# main.net
KiCad netlist of a schematic drawn in EasyEDA Pro
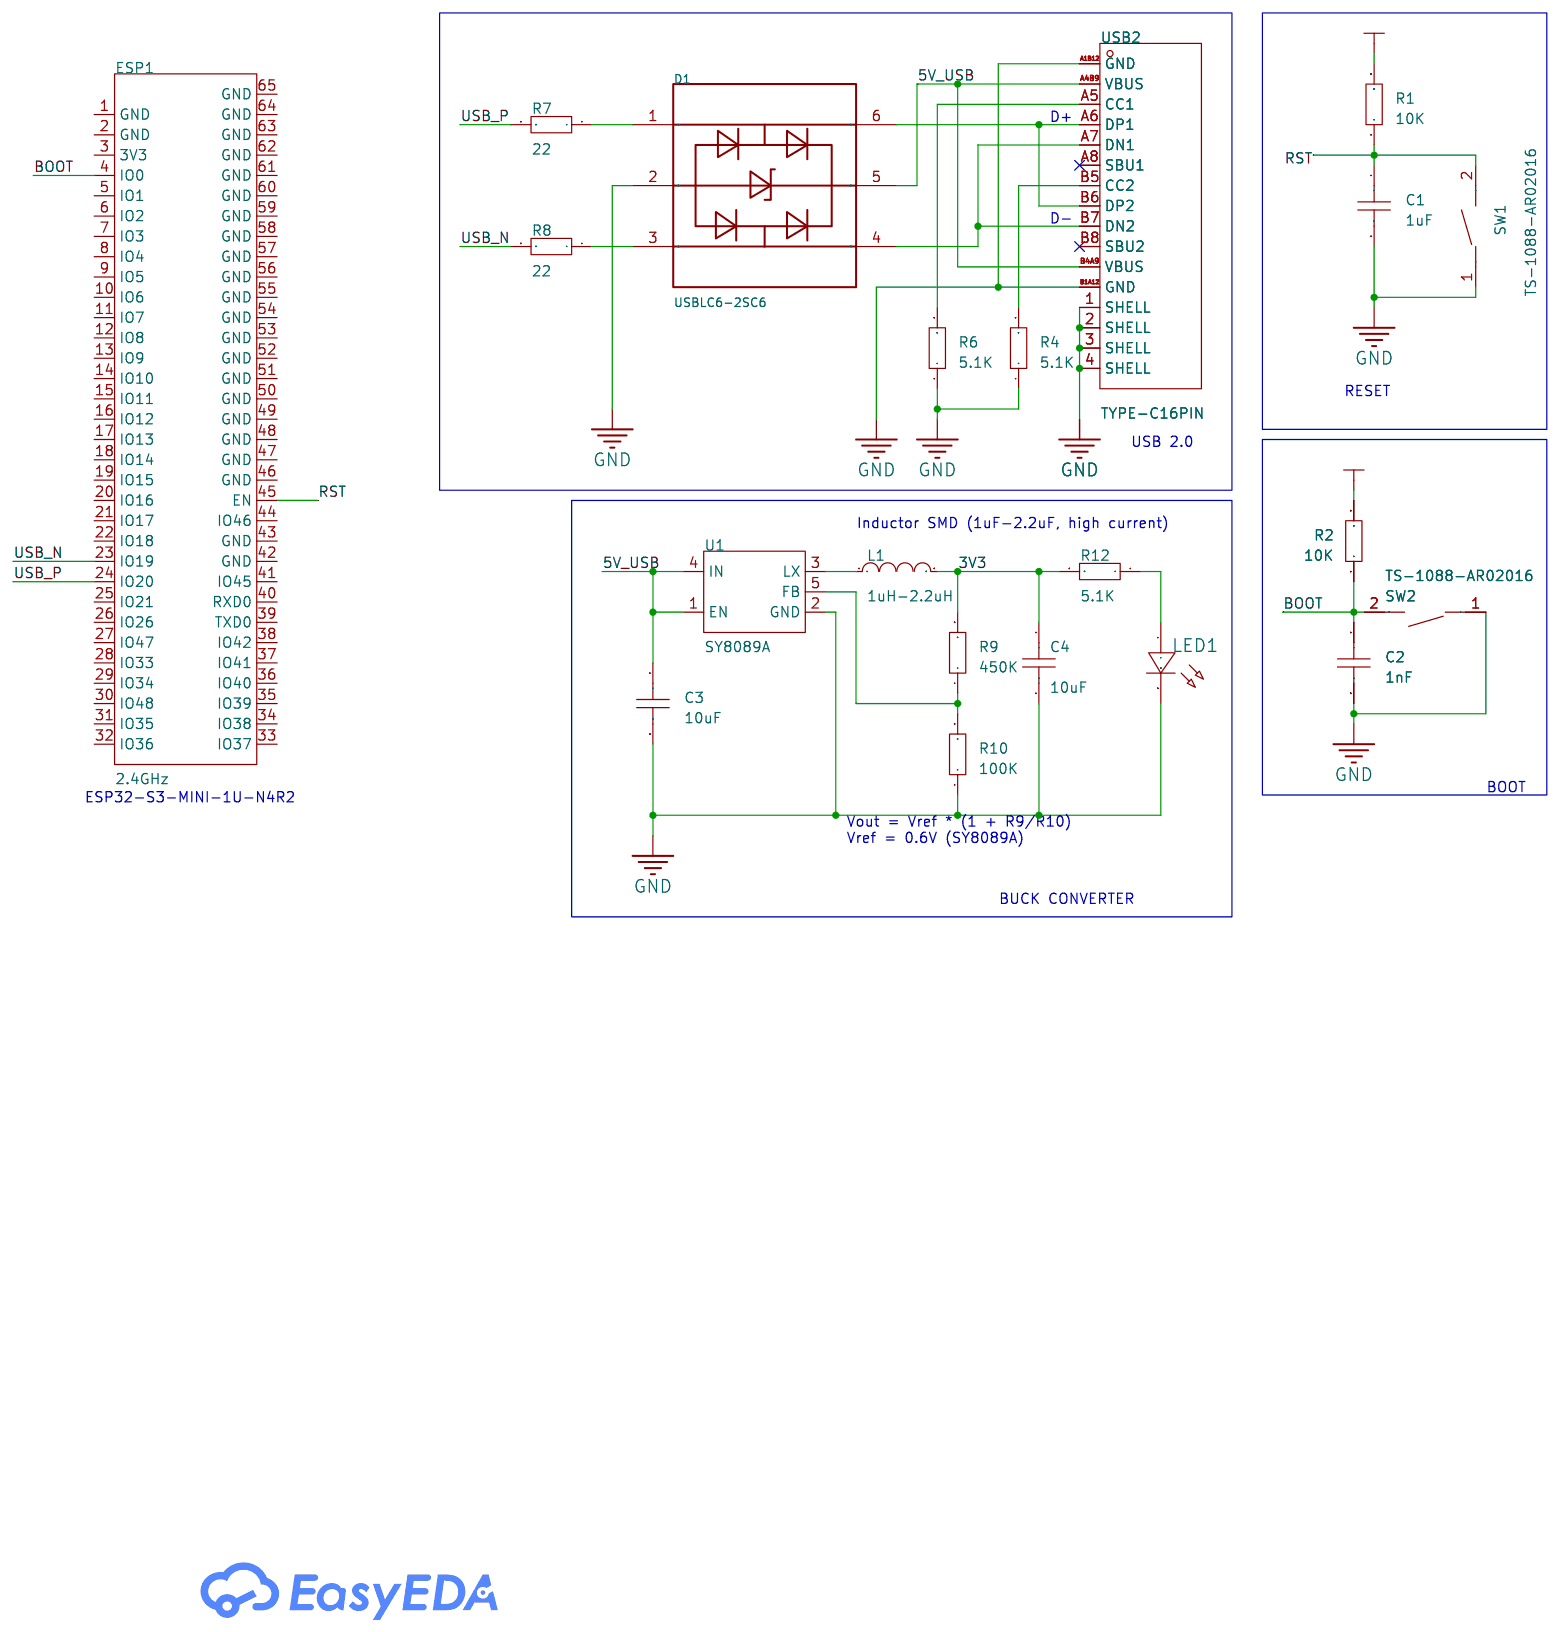
[diagram p0: ESP32-S3-Mini-1U-N4R2]
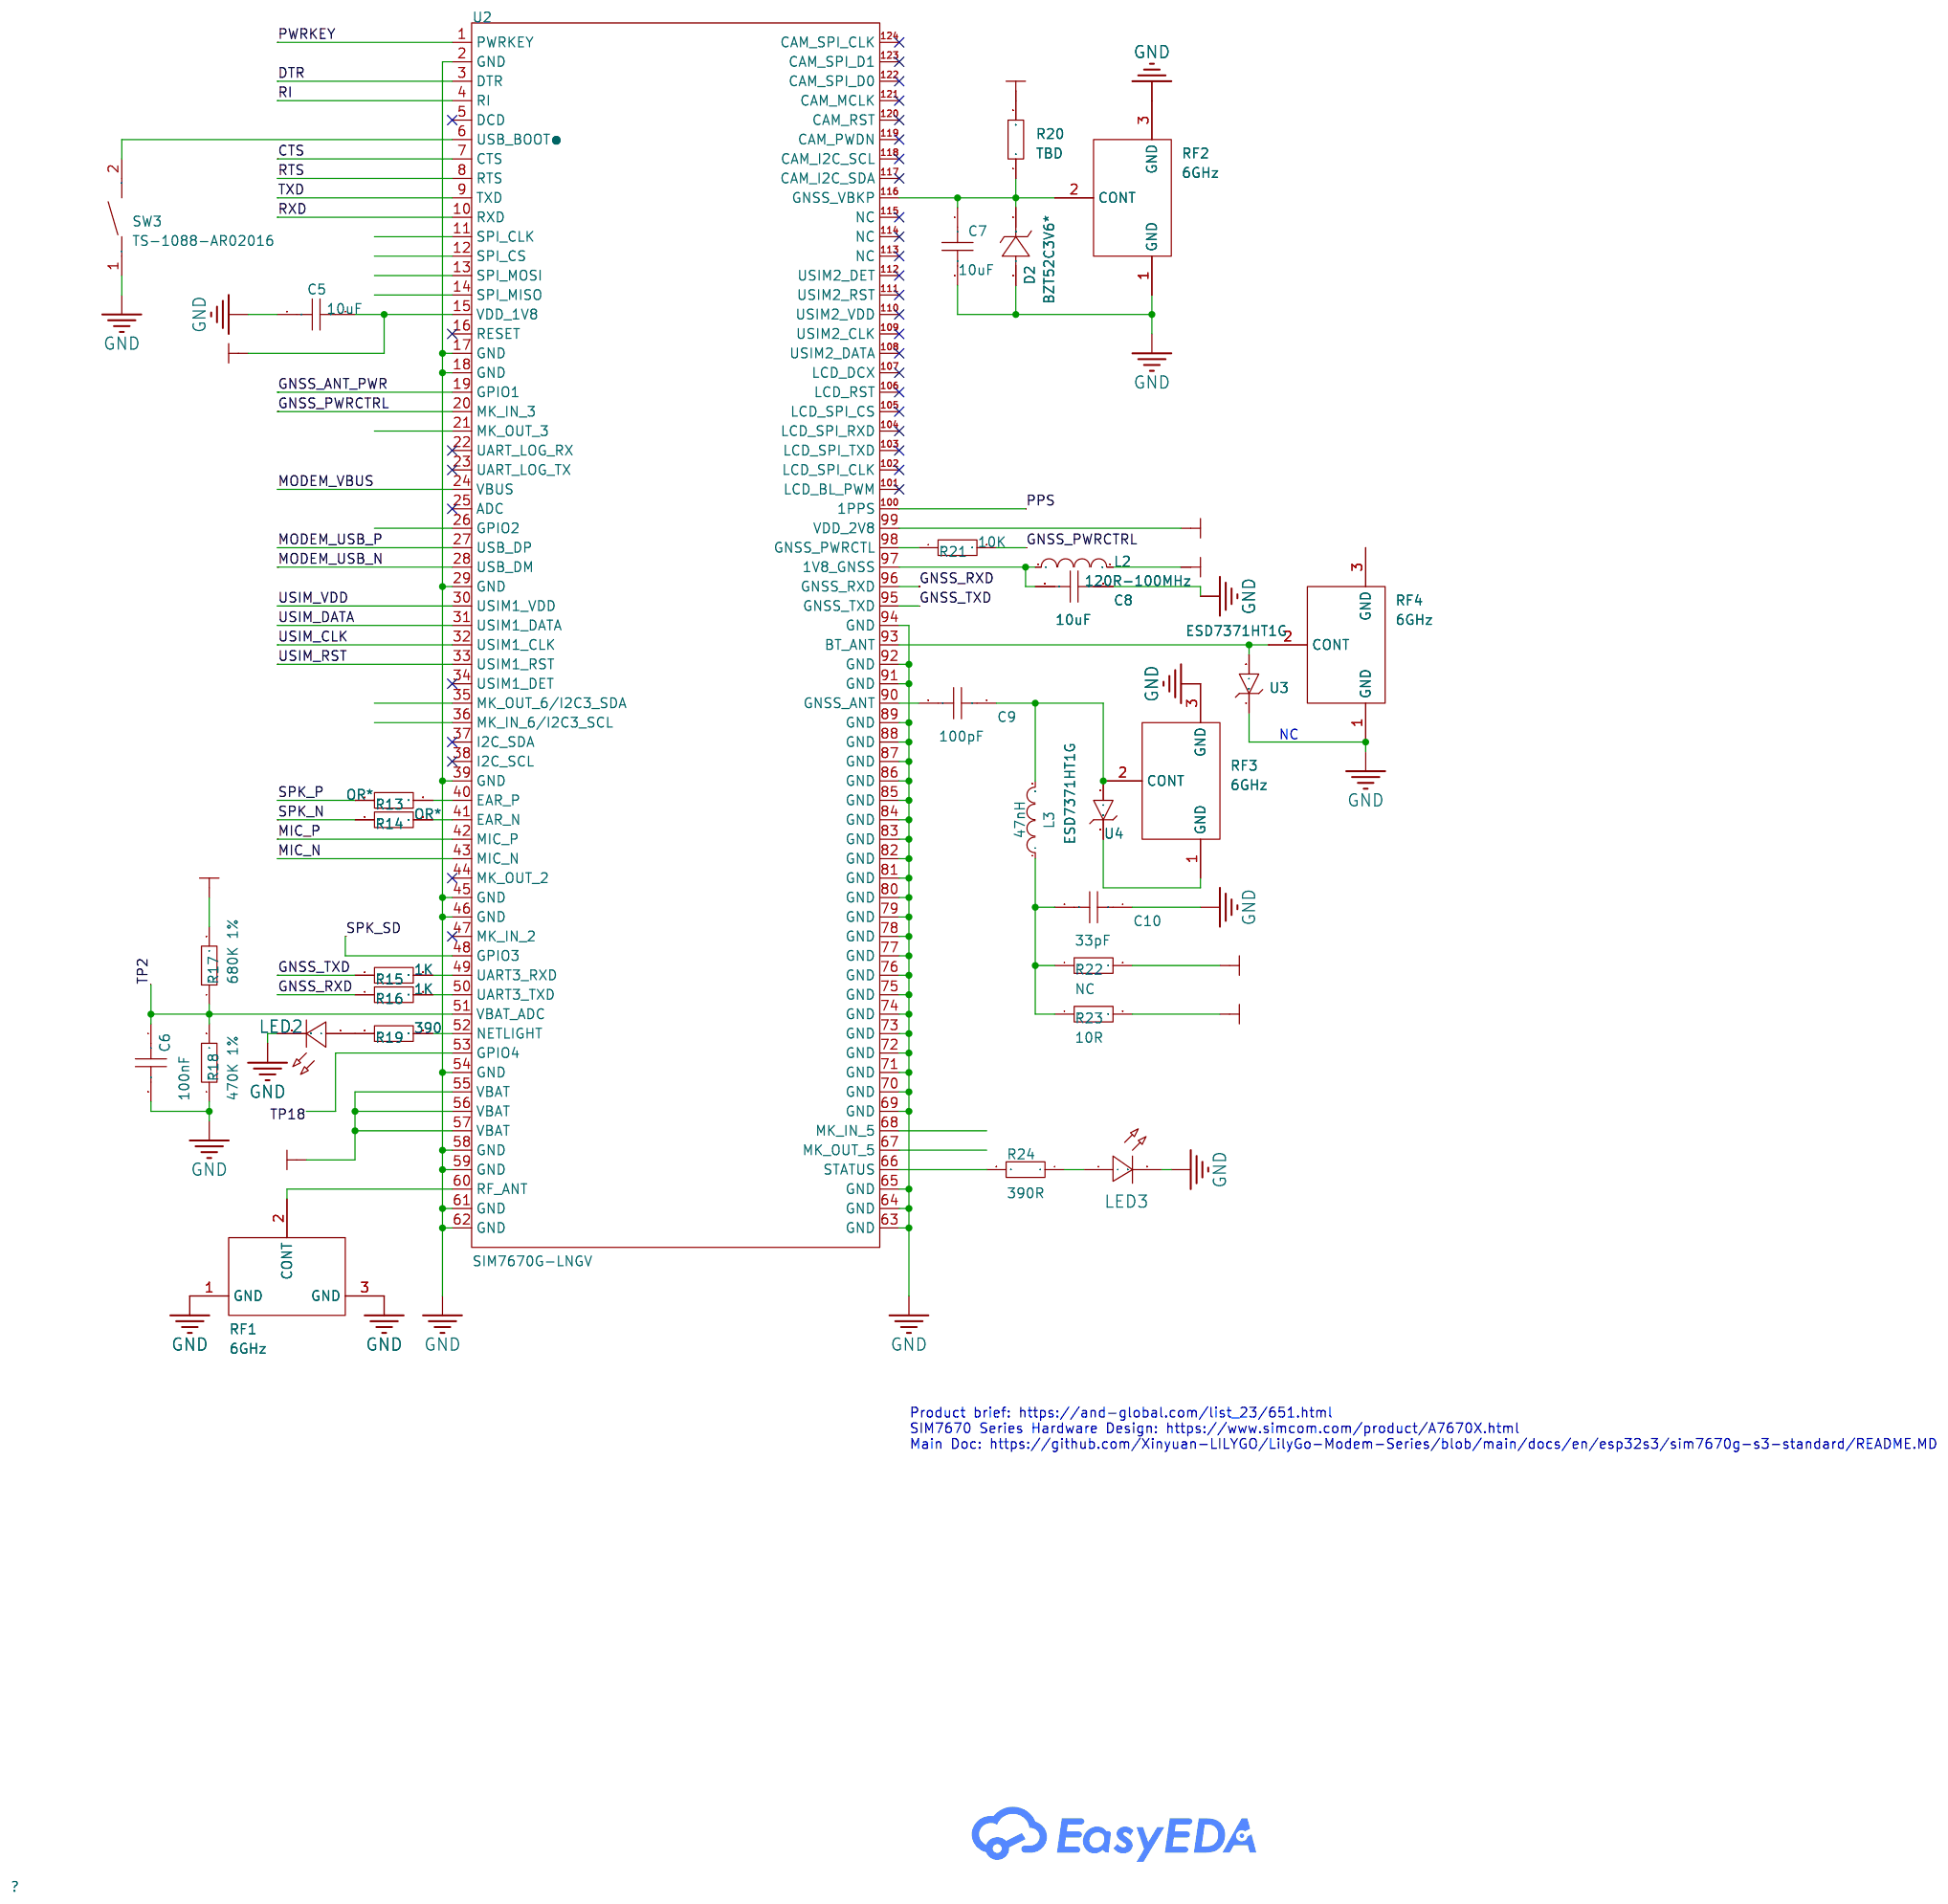
[diagram p1: SIM7670G]
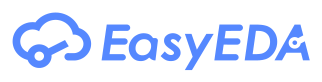
[diagram p2: SIM7670C]

(export (version "E")
  (design (tool "Eeschema 10.0.6"))
  (components
    (comp (ref "C1")
      (value "1uF")
      (footprint "easyedapro:C0603")
      (libsource (lib "easyedapro") (part "CAP_OLD"))
    )
    (comp (ref "C2")
      (value "1nF")
      (footprint "easyedapro:C0603")
      (libsource (lib "easyedapro") (part "CAP_OLD"))
    )
    (comp (ref "C3")
      (value "10uF")
      (footprint "easyedapro:C0603")
      (libsource (lib "easyedapro") (part "CAP_OLD"))
    )
    (comp (ref "C4")
      (value "10uF")
      (footprint "easyedapro:C0603")
      (libsource (lib "easyedapro") (part "CAP_OLD"))
    )
    (comp (ref "D1")
      (value "USBLC6-2SC6")
      (footprint "easyedapro:TSOT-23-6_L2.9-W1.6-P0.95-LS2.8-BR")
      (fields (field (name "Manufacturer") "Slkor(萨科微)"))
      (libsource (lib "easyedapro") (part "USBLC6-2SC6_C48971164"))
    )
    (comp (ref "ESP1")
      (value "2.4GHz")
      (footprint "easyedapro:BULETM-SMD_ESPRESSIF_ESP32-S3-MINI-1U-N8")
      (fields
        (field (name "Manufacturer Part") "ESP32-S3-MINI-1U-N4R2")
        (field (name "Manufacturer") "ESPRESSIF(乐鑫)")
      )
      (libsource (lib "easyedapro") (part "ESP32-S3-MINI-1U-N4R2"))
    )
    (comp (ref "L1")
      (value "1uH-2.2uH")
      (footprint "easyedapro:L0603")
      (libsource (lib "easyedapro") (part "电感"))
    )
    (comp (ref "LED1")
      (value "~")
      (footprint "easyedapro:LED0402-RD_YELLOW")
      (libsource (lib "easyedapro") (part "LED_R"))
    )
    (comp (ref "R1") (value "10K") (footprint "easyedapro:R0603") (libsource (lib "easyedapro") (part "Res")))
    (comp (ref "R2") (value "10K") (footprint "easyedapro:R0603") (libsource (lib "easyedapro") (part "Res")))
    (comp (ref "R4")
      (value "5.1K")
      (footprint "easyedapro:R0603")
      (libsource (lib "easyedapro") (part "Res"))
    )
    (comp (ref "R6")
      (value "5.1K")
      (footprint "easyedapro:R0603")
      (libsource (lib "easyedapro") (part "Res"))
    )
    (comp (ref "R7") (value "22") (footprint "easyedapro:R0603") (libsource (lib "easyedapro") (part "Res")))
    (comp (ref "R8") (value "22") (footprint "easyedapro:R0603") (libsource (lib "easyedapro") (part "Res")))
    (comp (ref "R9")
      (value "450K")
      (footprint "easyedapro:R0603")
      (libsource (lib "easyedapro") (part "Res"))
    )
    (comp (ref "R10")
      (value "100K")
      (footprint "easyedapro:R0603")
      (libsource (lib "easyedapro") (part "Res"))
    )
    (comp (ref "R12")
      (value "5.1K")
      (footprint "easyedapro:R0603")
      (libsource (lib "easyedapro") (part "Res"))
    )
    (comp (ref "SW1")
      (value "TS-1088-AR02016")
      (footprint "easyedapro:SW-SMD_L3.9-W3.0-P4.45")
      (fields (field (name "Manufacturer") "XUNPU(讯普)"))
      (libsource (lib "easyedapro") (part "TS-1088-AR02016"))
    )
    (comp (ref "SW2")
      (value "TS-1088-AR02016")
      (footprint "easyedapro:SW-SMD_L3.9-W3.0-P4.45")
      (fields (field (name "Manufacturer") "XUNPU(讯普)"))
      (libsource (lib "easyedapro") (part "TS-1088-AR02016"))
    )
    (comp (ref "U1")
      (value "SY8089A")
      (footprint "easyedapro:SOT-23-5_L3.0-W1.7-P0.95-LS2.8-BL")
      (fields (field (name "Manufacturer") "TECH PUBLIC(台舟)"))
      (libsource (lib "easyedapro") (part "SY8089A"))
    )
    (comp (ref "USB2")
      (value "TYPE-C16PIN")
      (footprint "easyedapro:USB-C-SMD_TYPE-C16PIN")
      (fields (field (name "Manufacturer") "SHOU HAN(首韩)"))
      (libsource (lib "easyedapro") (part "TYPE-C16PIN"))
    )
    (comp (ref "C5")
      (value "10uF")
      (footprint "easyedapro:C0603")
      (libsource (lib "easyedapro") (part "CAP_OLD"))
    )
    (comp (ref "C6")
      (value "100nF")
      (footprint "easyedapro:C0603")
      (libsource (lib "easyedapro") (part "CAP_OLD"))
    )
    (comp (ref "C7")
      (value "10uF")
      (footprint "easyedapro:C0603")
      (libsource (lib "easyedapro") (part "CAP_OLD"))
    )
    (comp (ref "C8")
      (value "10uF")
      (footprint "easyedapro:C0603")
      (libsource (lib "easyedapro") (part "CAP_OLD"))
    )
    (comp (ref "C9")
      (value "100pF")
      (footprint "easyedapro:C0603")
      (libsource (lib "easyedapro") (part "CAP_OLD"))
    )
    (comp (ref "C10")
      (value "33pF")
      (footprint "easyedapro:C0603")
      (libsource (lib "easyedapro") (part "CAP_OLD"))
    )
    (comp (ref "D2")
      (value "BZT52C3V6*")
      (footprint "easyedapro:SOD-123_L2.8-W1.8-LS3.7-RD")
      (fields (field (name "Manufacturer") "PAKER(派克微)"))
      (libsource (lib "easyedapro") (part "BZT52C3V6_C49652771"))
    )
    (comp (ref "L2")
      (value "120R-100MHz")
      (footprint "easyedapro:L0603")
      (libsource (lib "easyedapro") (part "电感"))
    )
    (comp (ref "L3") (value "47nH") (footprint "easyedapro:L0603") (libsource (lib "easyedapro") (part "电感")))
    (comp (ref "LED2")
      (value "~")
      (footprint "easyedapro:LED0402-RD_YELLOW")
      (libsource (lib "easyedapro") (part "LED_R"))
    )
    (comp (ref "LED3")
      (value "~")
      (footprint "easyedapro:LED0402-RD_YELLOW")
      (libsource (lib "easyedapro") (part "LED_R"))
    )
    (comp (ref "R13")
      (value "OR*")
      (footprint "easyedapro:R0603")
      (libsource (lib "easyedapro") (part "Res"))
    )
    (comp (ref "R14")
      (value "OR*")
      (footprint "easyedapro:R0603")
      (libsource (lib "easyedapro") (part "Res"))
    )
    (comp (ref "R15") (value "1K") (footprint "easyedapro:R0603") (libsource (lib "easyedapro") (part "Res")))
    (comp (ref "R16") (value "1K") (footprint "easyedapro:R0603") (libsource (lib "easyedapro") (part "Res")))
    (comp (ref "R17")
      (value "680K 1%")
      (footprint "easyedapro:R0603")
      (libsource (lib "easyedapro") (part "Res"))
    )
    (comp (ref "R18")
      (value "470K 1%")
      (footprint "easyedapro:R0603")
      (libsource (lib "easyedapro") (part "Res"))
    )
    (comp (ref "R19")
      (value "390")
      (footprint "easyedapro:R0603")
      (libsource (lib "easyedapro") (part "Res"))
    )
    (comp (ref "R20")
      (value "TBD")
      (footprint "easyedapro:R0603")
      (libsource (lib "easyedapro") (part "Res"))
    )
    (comp (ref "R21")
      (value "10K")
      (footprint "easyedapro:R0603")
      (libsource (lib "easyedapro") (part "Res"))
    )
    (comp (ref "R22") (value "NC") (footprint "easyedapro:R0603") (libsource (lib "easyedapro") (part "Res")))
    (comp (ref "R23")
      (value "10R")
      (footprint "easyedapro:R0603")
      (libsource (lib "easyedapro") (part "Res"))
    )
    (comp (ref "R24")
      (value "390R")
      (footprint "easyedapro:R0603")
      (libsource (lib "easyedapro") (part "Res"))
    )
    (comp (ref "RF1")
      (value "6GHz")
      (footprint "easyedapro:ANT-SMD_UFL-R-SMT01")
      (fields (field (name "Manufacturer Part") "U.FL-R-SMT(01)") (field (name "Manufacturer") "HRS(广濑)"))
      (libsource (lib "easyedapro") (part "U.FL-R-SMT(01)"))
    )
    (comp (ref "RF2")
      (value "6GHz")
      (footprint "easyedapro:ANT-SMD_UFL-R-SMT01")
      (fields (field (name "Manufacturer Part") "U.FL-R-SMT(01)") (field (name "Manufacturer") "HRS(广濑)"))
      (libsource (lib "easyedapro") (part "U.FL-R-SMT(01)"))
    )
    (comp (ref "RF3")
      (value "6GHz")
      (footprint "easyedapro:ANT-SMD_UFL-R-SMT01")
      (fields (field (name "Manufacturer Part") "U.FL-R-SMT(01)") (field (name "Manufacturer") "HRS(广濑)"))
      (libsource (lib "easyedapro") (part "U.FL-R-SMT(01)"))
    )
    (comp (ref "RF4")
      (value "6GHz")
      (footprint "easyedapro:ANT-SMD_UFL-R-SMT01")
      (fields (field (name "Manufacturer Part") "U.FL-R-SMT(01)") (field (name "Manufacturer") "HRS(广濑)"))
      (libsource (lib "easyedapro") (part "U.FL-R-SMT(01)"))
    )
    (comp (ref "SW3")
      (value "TS-1088-AR02016")
      (footprint "easyedapro:SW-SMD_L3.9-W3.0-P4.45")
      (fields (field (name "Manufacturer") "XUNPU(讯普)"))
      (libsource (lib "easyedapro") (part "TS-1088-AR02016"))
    )
    (comp (ref "U2")
      (value "SIM7670G-LNGV")
      (footprint "easyedapro:LCC-124_L24.0-W24.0-P1.0-TL")
      (fields (field (name "Manufacturer") "SIMCOM(芯讯通无线科技)"))
      (libsource (lib "easyedapro") (part "SIM7670G-LNGV"))
    )
    (comp (ref "U3")
      (value "ESD7371HT1G")
      (footprint "easyedapro:SOD-323_L1.7-W1.3-LS2.5-RD")
      (fields (field (name "Manufacturer") "onsemi(安森美)"))
      (libsource (lib "easyedapro") (part "ESD7371HT1G"))
    )
    (comp (ref "U4")
      (value "ESD7371HT1G")
      (footprint "easyedapro:SOD-323_L1.7-W1.3-LS2.5-RD")
      (fields (field (name "Manufacturer") "onsemi(安森美)"))
      (libsource (lib "easyedapro") (part "ESD7371HT1G"))
    )
  )
  (nets
    (net (code "1") (name "+1.8V") (class "Default")
      (node (ref "C5") (pin "1") (pinfunction "1_1") (pintype "input"))
      (node (ref "U2") (pin "15") (pinfunction "VDD_1V8_15") (pintype "unspecified"))
    )
    (net (code "2") (name "+1V8") (class "Default")
      (node (ref "L2") (pin "2") (pinfunction "2_2") (pintype "input"))
    )
    (net (code "3") (name "+3V6") (class "Default")
      (node (ref "U2") (pin "55") (pinfunction "VBAT_55") (pintype "unspecified"))
      (node (ref "U2") (pin "56") (pinfunction "VBAT_56") (pintype "unspecified"))
      (node (ref "U2") (pin "57") (pinfunction "VBAT_57") (pintype "unspecified"))
    )
    (net (code "4") (name "3.3V") (class "Default")
      (node (ref "R1") (pin "2") (pinfunction "2_2") (pintype "input"))
      (node (ref "R2") (pin "2") (pinfunction "2_2") (pintype "input"))
    )
    (net (code "5") (name "3V3") (class "Default")
      (node (ref "C4") (pin "1") (pinfunction "1_1") (pintype "input"))
      (node (ref "L1") (pin "2") (pinfunction "2_2") (pintype "input"))
      (node (ref "R12") (pin "2") (pinfunction "2_2") (pintype "input"))
      (node (ref "R9") (pin "2") (pinfunction "2_2") (pintype "input"))
    )
    (net (code "6") (name "5V_USB") (class "Default")
      (node (ref "C3") (pin "1") (pinfunction "1_1") (pintype "input"))
      (node (ref "D1") (pin "5") (pinfunction "VBUS_5") (pintype "input"))
      (node (ref "U1") (pin "1") (pinfunction "EN_1") (pintype "unspecified"))
      (node (ref "U1") (pin "4") (pinfunction "IN_4") (pintype "unspecified"))
      (node (ref "USB2") (pin "A4B9") (pinfunction "VBUS_A4B9") (pintype "unspecified"))
      (node (ref "USB2") (pin "B4A9") (pinfunction "VBUS_B4A9") (pintype "unspecified"))
    )
    (net (code "7") (name "BOOT") (class "Default")
      (node (ref "C2") (pin "1") (pinfunction "1_1") (pintype "input"))
      (node (ref "ESP1") (pin "4") (pinfunction "IO0_4") (pintype "unspecified"))
      (node (ref "R2") (pin "1") (pinfunction "1_1") (pintype "input"))
      (node (ref "SW2") (pin "2") (pinfunction "2_2") (pintype "unspecified"))
    )
    (net (code "8") (name "CTS") (class "Default")
      (node (ref "U2") (pin "7") (pinfunction "CTS_7") (pintype "unspecified"))
    )
    (net (code "9") (name "DTR") (class "Default")
      (node (ref "U2") (pin "3") (pinfunction "DTR_3") (pintype "unspecified"))
    )
    (net (code "10") (name "GND") (class "Default")
      (node (ref "C1") (pin "2") (pinfunction "2_2") (pintype "input"))
      (node (ref "C10") (pin "1") (pinfunction "1_1") (pintype "input"))
      (node (ref "C2") (pin "2") (pinfunction "2_2") (pintype "input"))
      (node (ref "C3") (pin "2") (pinfunction "2_2") (pintype "input"))
      (node (ref "C4") (pin "2") (pinfunction "2_2") (pintype "input"))
      (node (ref "C5") (pin "2") (pinfunction "2_2") (pintype "input"))
      (node (ref "C6") (pin "2") (pinfunction "2_2") (pintype "input"))
      (node (ref "C7") (pin "2") (pinfunction "2_2") (pintype "input"))
      (node (ref "C8") (pin "1") (pinfunction "1_1") (pintype "input"))
      (node (ref "D1") (pin "2") (pinfunction "GND_2") (pintype "input"))
      (node (ref "D2") (pin "2") (pinfunction "A_2") (pintype "unspecified"))
      (node (ref "LED1") (pin "2") (pinfunction "C_2") (pintype "input"))
      (node (ref "LED2") (pin "2") (pinfunction "C_2") (pintype "input"))
      (node (ref "LED3") (pin "2") (pinfunction "C_2") (pintype "input"))
      (node (ref "R10") (pin "1") (pinfunction "1_1") (pintype "input"))
      (node (ref "R18") (pin "1") (pinfunction "1_1") (pintype "input"))
      (node (ref "R4") (pin "1") (pinfunction "1_1") (pintype "input"))
      (node (ref "R6") (pin "1") (pinfunction "1_1") (pintype "input"))
      (node (ref "RF1") (pin "1") (pinfunction "GND_1") (pintype "unspecified"))
      (node (ref "RF1") (pin "3") (pinfunction "GND_3") (pintype "unspecified"))
      (node (ref "RF2") (pin "1") (pinfunction "GND_1") (pintype "unspecified"))
      (node (ref "RF2") (pin "3") (pinfunction "GND_3") (pintype "unspecified"))
      (node (ref "RF3") (pin "3") (pinfunction "GND_3") (pintype "unspecified"))
      (node (ref "RF4") (pin "1") (pinfunction "GND_1") (pintype "unspecified"))
      (node (ref "SW1") (pin "1") (pinfunction "1_1") (pintype "unspecified"))
      (node (ref "SW2") (pin "1") (pinfunction "1_1") (pintype "unspecified"))
      (node (ref "SW3") (pin "1") (pinfunction "1_1") (pintype "unspecified"))
      (node (ref "U1") (pin "2") (pinfunction "GND_2") (pintype "unspecified"))
      (node (ref "U2") (pin "17") (pinfunction "GND_17") (pintype "unspecified"))
      (node (ref "U2") (pin "18") (pinfunction "GND_18") (pintype "unspecified"))
      (node (ref "U2") (pin "2") (pinfunction "GND_2") (pintype "unspecified"))
      (node (ref "U2") (pin "29") (pinfunction "GND_29") (pintype "unspecified"))
      (node (ref "U2") (pin "39") (pinfunction "GND_39") (pintype "unspecified"))
      (node (ref "U2") (pin "45") (pinfunction "GND_45") (pintype "unspecified"))
      (node (ref "U2") (pin "46") (pinfunction "GND_46") (pintype "unspecified"))
      (node (ref "U2") (pin "54") (pinfunction "GND_54") (pintype "unspecified"))
      (node (ref "U2") (pin "58") (pinfunction "GND_58") (pintype "unspecified"))
      (node (ref "U2") (pin "59") (pinfunction "GND_59") (pintype "unspecified"))
      (node (ref "U2") (pin "61") (pinfunction "GND_61") (pintype "unspecified"))
      (node (ref "U2") (pin "62") (pinfunction "GND_62") (pintype "unspecified"))
      (node (ref "U2") (pin "63") (pinfunction "GND_63") (pintype "unspecified"))
      (node (ref "U2") (pin "64") (pinfunction "GND_64") (pintype "unspecified"))
      (node (ref "U2") (pin "65") (pinfunction "GND_65") (pintype "unspecified"))
      (node (ref "U2") (pin "69") (pinfunction "GND_69") (pintype "unspecified"))
      (node (ref "U2") (pin "70") (pinfunction "GND_70") (pintype "unspecified"))
      (node (ref "U2") (pin "71") (pinfunction "GND_71") (pintype "unspecified"))
      (node (ref "U2") (pin "72") (pinfunction "GND_72") (pintype "unspecified"))
      (node (ref "U2") (pin "73") (pinfunction "GND_73") (pintype "unspecified"))
      (node (ref "U2") (pin "74") (pinfunction "GND_74") (pintype "unspecified"))
      (node (ref "U2") (pin "75") (pinfunction "GND_75") (pintype "unspecified"))
      (node (ref "U2") (pin "76") (pinfunction "GND_76") (pintype "unspecified"))
      (node (ref "U2") (pin "77") (pinfunction "GND_77") (pintype "unspecified"))
      (node (ref "U2") (pin "78") (pinfunction "GND_78") (pintype "unspecified"))
      (node (ref "U2") (pin "79") (pinfunction "GND_79") (pintype "unspecified"))
      (node (ref "U2") (pin "80") (pinfunction "GND_80") (pintype "unspecified"))
      (node (ref "U2") (pin "81") (pinfunction "GND_81") (pintype "unspecified"))
      (node (ref "U2") (pin "82") (pinfunction "GND_82") (pintype "unspecified"))
      (node (ref "U2") (pin "83") (pinfunction "GND_83") (pintype "unspecified"))
      (node (ref "U2") (pin "84") (pinfunction "GND_84") (pintype "unspecified"))
      (node (ref "U2") (pin "85") (pinfunction "GND_85") (pintype "unspecified"))
      (node (ref "U2") (pin "86") (pinfunction "GND_86") (pintype "unspecified"))
      (node (ref "U2") (pin "87") (pinfunction "GND_87") (pintype "unspecified"))
      (node (ref "U2") (pin "88") (pinfunction "GND_88") (pintype "unspecified"))
      (node (ref "U2") (pin "89") (pinfunction "GND_89") (pintype "unspecified"))
      (node (ref "U2") (pin "91") (pinfunction "GND_91") (pintype "unspecified"))
      (node (ref "U2") (pin "92") (pinfunction "GND_92") (pintype "unspecified"))
      (node (ref "U2") (pin "94") (pinfunction "GND_94") (pintype "unspecified"))
      (node (ref "U3") (pin "1") (pinfunction "C_1") (pintype "unspecified"))
      (node (ref "USB2") (pin "1") (pinfunction "SHELL_1") (pintype "unspecified"))
      (node (ref "USB2") (pin "2") (pinfunction "SHELL_2") (pintype "unspecified"))
      (node (ref "USB2") (pin "3") (pinfunction "SHELL_3") (pintype "unspecified"))
      (node (ref "USB2") (pin "4") (pinfunction "SHELL_4") (pintype "unspecified"))
      (node (ref "USB2") (pin "A1B12") (pinfunction "GND_A1B12") (pintype "unspecified"))
      (node (ref "USB2") (pin "B1A12") (pinfunction "GND_B1A12") (pintype "unspecified"))
    )
    (net (code "11") (name "GNSS_ANT_PWR") (class "Default")
      (node (ref "U2") (pin "19") (pinfunction "GPIO1_19") (pintype "unspecified"))
    )
    (net (code "12") (name "GNSS_PWRCTRL") (class "Default")
      (node (ref "R21") (pin "2") (pinfunction "2_2") (pintype "input"))
      (node (ref "U2") (pin "20") (pinfunction "MK_IN_3_20") (pintype "unspecified"))
    )
    (net (code "13") (name "GNSS_RXD") (class "Default")
      (node (ref "R16") (pin "1") (pinfunction "1_1") (pintype "input"))
      (node (ref "U2") (pin "96") (pinfunction "GNSS_RXD_96") (pintype "unspecified"))
    )
    (net (code "14") (name "GNSS_TXD") (class "Default")
      (node (ref "R15") (pin "1") (pinfunction "1_1") (pintype "input"))
      (node (ref "U2") (pin "95") (pinfunction "GNSS_TXD_95") (pintype "unspecified"))
    )
    (net (code "15") (name "MIC_N") (class "Default")
      (node (ref "U2") (pin "43") (pinfunction "MIC_N_43") (pintype "unspecified"))
    )
    (net (code "16") (name "MIC_P") (class "Default")
      (node (ref "U2") (pin "42") (pinfunction "MIC_P_42") (pintype "unspecified"))
    )
    (net (code "17") (name "MODEM_USB_N") (class "Default")
      (node (ref "U2") (pin "28") (pinfunction "USB_DM_28") (pintype "unspecified"))
    )
    (net (code "18") (name "MODEM_USB_P") (class "Default")
      (node (ref "U2") (pin "27") (pinfunction "USB_DP_27") (pintype "unspecified"))
    )
    (net (code "19") (name "MODEM_VBUS") (class "Default")
      (node (ref "U2") (pin "24") (pinfunction "VBUS_24") (pintype "unspecified"))
    )
    (net (code "20") (name "Net-(C10-Pad2)") (class "Default")
      (node (ref "C10") (pin "2") (pinfunction "2_2") (pintype "input"))
      (node (ref "L3") (pin "1") (pinfunction "1_1") (pintype "input"))
      (node (ref "R22") (pin "1") (pinfunction "1_1") (pintype "input"))
      (node (ref "R23") (pin "1") (pinfunction "1_1") (pintype "input"))
    )
    (net (code "21") (name "Net-(D1-I{slash}O1-Pad1)") (class "Default")
      (node (ref "D1") (pin "1") (pinfunction "I/O1_1") (pintype "input"))
      (node (ref "R7") (pin "1") (pinfunction "1_1") (pintype "input"))
    )
    (net (code "22") (name "Net-(D1-I{slash}O2-Pad3)") (class "Default")
      (node (ref "D1") (pin "3") (pinfunction "I/O2_3") (pintype "input"))
      (node (ref "R8") (pin "1") (pinfunction "1_1") (pintype "input"))
    )
    (net (code "23") (name "Net-(D2-C)") (class "Default")
      (node (ref "C7") (pin "1") (pinfunction "1_1") (pintype "input"))
      (node (ref "D2") (pin "1") (pinfunction "C_1") (pintype "unspecified"))
      (node (ref "R20") (pin "1") (pinfunction "1_1") (pintype "input"))
      (node (ref "RF2") (pin "2") (pinfunction "CONT_2") (pintype "unspecified"))
      (node (ref "U2") (pin "116") (pinfunction "GNSS_VBKP_116") (pintype "unspecified"))
    )
    (net (code "24") (name "Net-(LED1-A)") (class "Default")
      (node (ref "LED1") (pin "1") (pinfunction "A_1") (pintype "input"))
      (node (ref "R12") (pin "1") (pinfunction "1_1") (pintype "input"))
    )
    (net (code "25") (name "Net-(LED2-A)") (class "Default")
      (node (ref "LED2") (pin "1") (pinfunction "A_1") (pintype "input"))
      (node (ref "R19") (pin "1") (pinfunction "1_1") (pintype "input"))
    )
    (net (code "26") (name "Net-(LED3-A)") (class "Default")
      (node (ref "LED3") (pin "1") (pinfunction "A_1") (pintype "input"))
      (node (ref "R24") (pin "1") (pinfunction "1_1") (pintype "input"))
    )
    (net (code "27") (name "Net-(RF1-CONT)") (class "Default")
      (node (ref "RF1") (pin "2") (pinfunction "CONT_2") (pintype "unspecified"))
      (node (ref "U2") (pin "60") (pinfunction "RF_ANT_60") (pintype "unspecified"))
    )
    (net (code "28") (name "Net-(RF3-CONT)") (class "Default")
      (node (ref "C9") (pin "1") (pinfunction "1_1") (pintype "input"))
      (node (ref "L3") (pin "2") (pinfunction "2_2") (pintype "input"))
      (node (ref "RF3") (pin "2") (pinfunction "CONT_2") (pintype "unspecified"))
      (node (ref "U4") (pin "2") (pinfunction "A_2") (pintype "unspecified"))
    )
    (net (code "29") (name "Net-(RF4-CONT)") (class "Default")
      (node (ref "RF4") (pin "2") (pinfunction "CONT_2") (pintype "unspecified"))
      (node (ref "U2") (pin "93") (pinfunction "BT_ANT_93") (pintype "unspecified"))
      (node (ref "U3") (pin "2") (pinfunction "A_2") (pintype "unspecified"))
    )
    (net (code "30") (name "Net-(U1-FB)") (class "Default")
      (node (ref "R10") (pin "2") (pinfunction "2_2") (pintype "input"))
      (node (ref "R9") (pin "1") (pinfunction "1_1") (pintype "input"))
      (node (ref "U1") (pin "5") (pinfunction "FB_5") (pintype "unspecified"))
    )
    (net (code "31") (name "Net-(U1-LX)") (class "Default")
      (node (ref "L1") (pin "1") (pinfunction "1_1") (pintype "input"))
      (node (ref "U1") (pin "3") (pinfunction "LX_3") (pintype "unspecified"))
    )
    (net (code "32") (name "Net-(U2-1V8_GNSS)") (class "Default")
      (node (ref "C8") (pin "2") (pinfunction "2_2") (pintype "input"))
      (node (ref "L2") (pin "1") (pinfunction "1_1") (pintype "input"))
      (node (ref "U2") (pin "97") (pinfunction "1V8_GNSS_97") (pintype "unspecified"))
    )
    (net (code "33") (name "Net-(U2-EAR_N)") (class "Default")
      (node (ref "R14") (pin "2") (pinfunction "2_2") (pintype "input"))
      (node (ref "U2") (pin "41") (pinfunction "EAR_N_41") (pintype "unspecified"))
    )
    (net (code "34") (name "Net-(U2-EAR_P)") (class "Default")
      (node (ref "R13") (pin "2") (pinfunction "2_2") (pintype "input"))
      (node (ref "U2") (pin "40") (pinfunction "EAR_P_40") (pintype "unspecified"))
    )
    (net (code "35") (name "Net-(U2-GNSS_ANT)") (class "Default")
      (node (ref "C9") (pin "2") (pinfunction "2_2") (pintype "input"))
      (node (ref "U2") (pin "90") (pinfunction "GNSS_ANT_90") (pintype "unspecified"))
    )
    (net (code "36") (name "Net-(U2-GNSS_PWRCTL)") (class "Default")
      (node (ref "R21") (pin "1") (pinfunction "1_1") (pintype "input"))
      (node (ref "U2") (pin "98") (pinfunction "GNSS_PWRCTL_98") (pintype "unspecified"))
    )
    (net (code "37") (name "Net-(U2-NETLIGHT)") (class "Default")
      (node (ref "R19") (pin "2") (pinfunction "2_2") (pintype "input"))
      (node (ref "U2") (pin "52") (pinfunction "NETLIGHT_52") (pintype "unspecified"))
    )
    (net (code "38") (name "Net-(U2-STATUS)") (class "Default")
      (node (ref "R24") (pin "2") (pinfunction "2_2") (pintype "input"))
      (node (ref "U2") (pin "66") (pinfunction "STATUS_66") (pintype "unspecified"))
    )
    (net (code "39") (name "Net-(U2-UART3_RXD)") (class "Default")
      (node (ref "R15") (pin "2") (pinfunction "2_2") (pintype "input"))
      (node (ref "U2") (pin "49") (pinfunction "UART3_RXD_49") (pintype "unspecified"))
    )
    (net (code "40") (name "Net-(U2-UART3_TXD)") (class "Default")
      (node (ref "R16") (pin "2") (pinfunction "2_2") (pintype "input"))
      (node (ref "U2") (pin "50") (pinfunction "UART3_TXD_50") (pintype "unspecified"))
    )
    (net (code "41") (name "Net-(U2-USB_BOOT●)") (class "Default")
      (node (ref "SW3") (pin "2") (pinfunction "2_2") (pintype "unspecified"))
      (node (ref "U2") (pin "6") (pinfunction "USB_BOOT●_6") (pintype "unspecified"))
    )
    (net (code "42") (name "Net-(U4-C)") (class "Default")
      (node (ref "RF3") (pin "1") (pinfunction "GND_1") (pintype "unspecified"))
      (node (ref "U4") (pin "1") (pinfunction "C_1") (pintype "unspecified"))
    )
    (net (code "43") (name "Net-(USB2-CC1)") (class "Default")
      (node (ref "R6") (pin "2") (pinfunction "2_2") (pintype "input"))
      (node (ref "USB2") (pin "A5") (pinfunction "CC1_A5") (pintype "unspecified"))
    )
    (net (code "44") (name "Net-(USB2-CC2)") (class "Default")
      (node (ref "R4") (pin "2") (pinfunction "2_2") (pintype "input"))
      (node (ref "USB2") (pin "B5") (pinfunction "CC2_B5") (pintype "unspecified"))
    )
    (net (code "45") (name "Net-(USB2-DN1)") (class "Default")
      (node (ref "D1") (pin "4") (pinfunction "I/O2_4") (pintype "input"))
      (node (ref "USB2") (pin "A7") (pinfunction "DN1_A7") (pintype "unspecified"))
      (node (ref "USB2") (pin "B7") (pinfunction "DN2_B7") (pintype "unspecified"))
    )
    (net (code "46") (name "Net-(USB2-DP1)") (class "Default")
      (node (ref "D1") (pin "6") (pinfunction "I/O1_6") (pintype "input"))
      (node (ref "USB2") (pin "A6") (pinfunction "DP1_A6") (pintype "unspecified"))
      (node (ref "USB2") (pin "B6") (pinfunction "DP2_B6") (pintype "unspecified"))
    )
    (net (code "47") (name "PPS") (class "Default")
      (node (ref "U2") (pin "100") (pinfunction "1PPS_100") (pintype "unspecified"))
    )
    (net (code "48") (name "PWRKEY") (class "Default")
      (node (ref "U2") (pin "1") (pinfunction "PWRKEY_1") (pintype "unspecified"))
    )
    (net (code "49") (name "RI") (class "Default")
      (node (ref "U2") (pin "4") (pinfunction "RI_4") (pintype "unspecified"))
    )
    (net (code "50") (name "RST") (class "Default")
      (node (ref "C1") (pin "1") (pinfunction "1_1") (pintype "input"))
      (node (ref "ESP1") (pin "45") (pinfunction "EN_45") (pintype "unspecified"))
      (node (ref "R1") (pin "1") (pinfunction "1_1") (pintype "input"))
      (node (ref "SW1") (pin "2") (pinfunction "2_2") (pintype "unspecified"))
    )
    (net (code "51") (name "RTS") (class "Default")
      (node (ref "U2") (pin "8") (pinfunction "RTS_8") (pintype "unspecified"))
    )
    (net (code "52") (name "RXD") (class "Default")
      (node (ref "U2") (pin "10") (pinfunction "RXD_10") (pintype "unspecified"))
    )
    (net (code "53") (name "SPK_N") (class "Default")
      (node (ref "R14") (pin "1") (pinfunction "1_1") (pintype "input"))
    )
    (net (code "54") (name "SPK_P") (class "Default")
      (node (ref "R13") (pin "1") (pinfunction "1_1") (pintype "input"))
    )
    (net (code "55") (name "SPK_SD") (class "Default")
      (node (ref "U2") (pin "48") (pinfunction "GPIO3_48") (pintype "unspecified"))
    )
    (net (code "56") (name "TP2") (class "Default")
      (node (ref "C6") (pin "1") (pinfunction "1_1") (pintype "input"))
      (node (ref "R17") (pin "1") (pinfunction "1_1") (pintype "input"))
      (node (ref "R18") (pin "2") (pinfunction "2_2") (pintype "input"))
      (node (ref "U2") (pin "51") (pinfunction "VBAT_ADC_51") (pintype "unspecified"))
    )
    (net (code "57") (name "TP18") (class "Default")
      (node (ref "U2") (pin "53") (pinfunction "GPIO4_53") (pintype "unspecified"))
    )
    (net (code "58") (name "TXD") (class "Default")
      (node (ref "U2") (pin "9") (pinfunction "TXD_9") (pintype "unspecified"))
    )
    (net (code "59") (name "USB_N") (class "Default")
      (node (ref "ESP1") (pin "23") (pinfunction "IO19_23") (pintype "unspecified"))
      (node (ref "R8") (pin "2") (pinfunction "2_2") (pintype "input"))
    )
    (net (code "60") (name "USB_P") (class "Default")
      (node (ref "ESP1") (pin "24") (pinfunction "IO20_24") (pintype "unspecified"))
      (node (ref "R7") (pin "2") (pinfunction "2_2") (pintype "input"))
    )
    (net (code "61") (name "USIM_CLK") (class "Default")
      (node (ref "U2") (pin "32") (pinfunction "USIM1_CLK_32") (pintype "unspecified"))
    )
    (net (code "62") (name "USIM_DATA") (class "Default")
      (node (ref "U2") (pin "31") (pinfunction "USIM1_DATA_31") (pintype "unspecified"))
    )
    (net (code "63") (name "USIM_RST") (class "Default")
      (node (ref "U2") (pin "33") (pinfunction "USIM1_RST_33") (pintype "unspecified"))
    )
    (net (code "64") (name "USIM_VDD") (class "Default")
      (node (ref "U2") (pin "30") (pinfunction "USIM1_VDD_30") (pintype "unspecified"))
    )
    (net (code "65") (name "VBAT") (class "Default")
      (node (ref "R17") (pin "2") (pinfunction "2_2") (pintype "input"))
    )
    (net (code "66") (name "VDD_AUX") (class "Default")
      (node (ref "R22") (pin "2") (pinfunction "2_2") (pintype "input"))
      (node (ref "U2") (pin "99") (pinfunction "VDD_2V8_99") (pintype "unspecified"))
    )
    (net (code "67") (name "VDD_GPS") (class "Default")
      (node (ref "R20") (pin "2") (pinfunction "2_2") (pintype "input"))
      (node (ref "R23") (pin "2") (pinfunction "2_2") (pintype "input"))
    )
    (net (code "68") (name "unconnected-(ESP1-3V3-Pad3)") (class "Default")
      (node (ref "ESP1") (pin "3") (pinfunction "3V3_3") (pintype "unspecified"))
    )
    (net (code "69") (name "unconnected-(ESP1-GND-Pad1)") (class "Default")
      (node (ref "ESP1") (pin "1") (pinfunction "GND_1") (pintype "unspecified"))
    )
    (net (code "70") (name "unconnected-(ESP1-GND-Pad2)") (class "Default")
      (node (ref "ESP1") (pin "2") (pinfunction "GND_2") (pintype "unspecified"))
    )
    (net (code "71") (name "unconnected-(ESP1-GND-Pad42)") (class "Default")
      (node (ref "ESP1") (pin "42") (pinfunction "GND_42") (pintype "unspecified"))
    )
    (net (code "72") (name "unconnected-(ESP1-GND-Pad43)") (class "Default")
      (node (ref "ESP1") (pin "43") (pinfunction "GND_43") (pintype "unspecified"))
    )
    (net (code "73") (name "unconnected-(ESP1-GND-Pad46)") (class "Default")
      (node (ref "ESP1") (pin "46") (pinfunction "GND_46") (pintype "unspecified"))
    )
    (net (code "74") (name "unconnected-(ESP1-GND-Pad47)") (class "Default")
      (node (ref "ESP1") (pin "47") (pinfunction "GND_47") (pintype "unspecified"))
    )
    (net (code "75") (name "unconnected-(ESP1-GND-Pad48)") (class "Default")
      (node (ref "ESP1") (pin "48") (pinfunction "GND_48") (pintype "unspecified"))
    )
    (net (code "76") (name "unconnected-(ESP1-GND-Pad49)") (class "Default")
      (node (ref "ESP1") (pin "49") (pinfunction "GND_49") (pintype "unspecified"))
    )
    (net (code "77") (name "unconnected-(ESP1-GND-Pad50)") (class "Default")
      (node (ref "ESP1") (pin "50") (pinfunction "GND_50") (pintype "unspecified"))
    )
    (net (code "78") (name "unconnected-(ESP1-GND-Pad51)") (class "Default")
      (node (ref "ESP1") (pin "51") (pinfunction "GND_51") (pintype "unspecified"))
    )
    (net (code "79") (name "unconnected-(ESP1-GND-Pad52)") (class "Default")
      (node (ref "ESP1") (pin "52") (pinfunction "GND_52") (pintype "unspecified"))
    )
    (net (code "80") (name "unconnected-(ESP1-GND-Pad53)") (class "Default")
      (node (ref "ESP1") (pin "53") (pinfunction "GND_53") (pintype "unspecified"))
    )
    (net (code "81") (name "unconnected-(ESP1-GND-Pad54)") (class "Default")
      (node (ref "ESP1") (pin "54") (pinfunction "GND_54") (pintype "unspecified"))
    )
    (net (code "82") (name "unconnected-(ESP1-GND-Pad55)") (class "Default")
      (node (ref "ESP1") (pin "55") (pinfunction "GND_55") (pintype "unspecified"))
    )
    (net (code "83") (name "unconnected-(ESP1-GND-Pad56)") (class "Default")
      (node (ref "ESP1") (pin "56") (pinfunction "GND_56") (pintype "unspecified"))
    )
    (net (code "84") (name "unconnected-(ESP1-GND-Pad57)") (class "Default")
      (node (ref "ESP1") (pin "57") (pinfunction "GND_57") (pintype "unspecified"))
    )
    (net (code "85") (name "unconnected-(ESP1-GND-Pad58)") (class "Default")
      (node (ref "ESP1") (pin "58") (pinfunction "GND_58") (pintype "unspecified"))
    )
    (net (code "86") (name "unconnected-(ESP1-GND-Pad59)") (class "Default")
      (node (ref "ESP1") (pin "59") (pinfunction "GND_59") (pintype "unspecified"))
    )
    (net (code "87") (name "unconnected-(ESP1-GND-Pad60)") (class "Default")
      (node (ref "ESP1") (pin "60") (pinfunction "GND_60") (pintype "unspecified"))
    )
    (net (code "88") (name "unconnected-(ESP1-GND-Pad61)") (class "Default")
      (node (ref "ESP1") (pin "61") (pinfunction "GND_61") (pintype "unspecified"))
    )
    (net (code "89") (name "unconnected-(ESP1-GND-Pad62)") (class "Default")
      (node (ref "ESP1") (pin "62") (pinfunction "GND_62") (pintype "unspecified"))
    )
    (net (code "90") (name "unconnected-(ESP1-GND-Pad63)") (class "Default")
      (node (ref "ESP1") (pin "63") (pinfunction "GND_63") (pintype "unspecified"))
    )
    (net (code "91") (name "unconnected-(ESP1-GND-Pad64)") (class "Default")
      (node (ref "ESP1") (pin "64") (pinfunction "GND_64") (pintype "unspecified"))
    )
    (net (code "92") (name "unconnected-(ESP1-GND-Pad65)") (class "Default")
      (node (ref "ESP1") (pin "65") (pinfunction "GND_65") (pintype "unspecified"))
    )
    (net (code "93") (name "unconnected-(ESP1-IO1-Pad5)") (class "Default")
      (node (ref "ESP1") (pin "5") (pinfunction "IO1_5") (pintype "unspecified"))
    )
    (net (code "94") (name "unconnected-(ESP1-IO2-Pad6)") (class "Default")
      (node (ref "ESP1") (pin "6") (pinfunction "IO2_6") (pintype "unspecified"))
    )
    (net (code "95") (name "unconnected-(ESP1-IO3-Pad7)") (class "Default")
      (node (ref "ESP1") (pin "7") (pinfunction "IO3_7") (pintype "unspecified"))
    )
    (net (code "96") (name "unconnected-(ESP1-IO4-Pad8)") (class "Default")
      (node (ref "ESP1") (pin "8") (pinfunction "IO4_8") (pintype "unspecified"))
    )
    (net (code "97") (name "unconnected-(ESP1-IO5-Pad9)") (class "Default")
      (node (ref "ESP1") (pin "9") (pinfunction "IO5_9") (pintype "unspecified"))
    )
    (net (code "98") (name "unconnected-(ESP1-IO6-Pad10)") (class "Default")
      (node (ref "ESP1") (pin "10") (pinfunction "IO6_10") (pintype "unspecified"))
    )
    (net (code "99") (name "unconnected-(ESP1-IO7-Pad11)") (class "Default")
      (node (ref "ESP1") (pin "11") (pinfunction "IO7_11") (pintype "unspecified"))
    )
    (net (code "100") (name "unconnected-(ESP1-IO8-Pad12)") (class "Default")
      (node (ref "ESP1") (pin "12") (pinfunction "IO8_12") (pintype "unspecified"))
    )
    (net (code "101") (name "unconnected-(ESP1-IO9-Pad13)") (class "Default")
      (node (ref "ESP1") (pin "13") (pinfunction "IO9_13") (pintype "unspecified"))
    )
    (net (code "102") (name "unconnected-(ESP1-IO10-Pad14)") (class "Default")
      (node (ref "ESP1") (pin "14") (pinfunction "IO10_14") (pintype "unspecified"))
    )
    (net (code "103") (name "unconnected-(ESP1-IO11-Pad15)") (class "Default")
      (node (ref "ESP1") (pin "15") (pinfunction "IO11_15") (pintype "unspecified"))
    )
    (net (code "104") (name "unconnected-(ESP1-IO12-Pad16)") (class "Default")
      (node (ref "ESP1") (pin "16") (pinfunction "IO12_16") (pintype "unspecified"))
    )
    (net (code "105") (name "unconnected-(ESP1-IO13-Pad17)") (class "Default")
      (node (ref "ESP1") (pin "17") (pinfunction "IO13_17") (pintype "unspecified"))
    )
    (net (code "106") (name "unconnected-(ESP1-IO14-Pad18)") (class "Default")
      (node (ref "ESP1") (pin "18") (pinfunction "IO14_18") (pintype "unspecified"))
    )
    (net (code "107") (name "unconnected-(ESP1-IO15-Pad19)") (class "Default")
      (node (ref "ESP1") (pin "19") (pinfunction "IO15_19") (pintype "unspecified"))
    )
    (net (code "108") (name "unconnected-(ESP1-IO16-Pad20)") (class "Default")
      (node (ref "ESP1") (pin "20") (pinfunction "IO16_20") (pintype "unspecified"))
    )
    (net (code "109") (name "unconnected-(ESP1-IO17-Pad21)") (class "Default")
      (node (ref "ESP1") (pin "21") (pinfunction "IO17_21") (pintype "unspecified"))
    )
    (net (code "110") (name "unconnected-(ESP1-IO18-Pad22)") (class "Default")
      (node (ref "ESP1") (pin "22") (pinfunction "IO18_22") (pintype "unspecified"))
    )
    (net (code "111") (name "unconnected-(ESP1-IO21-Pad25)") (class "Default")
      (node (ref "ESP1") (pin "25") (pinfunction "IO21_25") (pintype "unspecified"))
    )
    (net (code "112") (name "unconnected-(ESP1-IO26-Pad26)") (class "Default")
      (node (ref "ESP1") (pin "26") (pinfunction "IO26_26") (pintype "unspecified"))
    )
    (net (code "113") (name "unconnected-(ESP1-IO33-Pad28)") (class "Default")
      (node (ref "ESP1") (pin "28") (pinfunction "IO33_28") (pintype "unspecified"))
    )
    (net (code "114") (name "unconnected-(ESP1-IO34-Pad29)") (class "Default")
      (node (ref "ESP1") (pin "29") (pinfunction "IO34_29") (pintype "unspecified"))
    )
    (net (code "115") (name "unconnected-(ESP1-IO35-Pad31)") (class "Default")
      (node (ref "ESP1") (pin "31") (pinfunction "IO35_31") (pintype "unspecified"))
    )
    (net (code "116") (name "unconnected-(ESP1-IO36-Pad32)") (class "Default")
      (node (ref "ESP1") (pin "32") (pinfunction "IO36_32") (pintype "unspecified"))
    )
    (net (code "117") (name "unconnected-(ESP1-IO37-Pad33)") (class "Default")
      (node (ref "ESP1") (pin "33") (pinfunction "IO37_33") (pintype "unspecified"))
    )
    (net (code "118") (name "unconnected-(ESP1-IO38-Pad34)") (class "Default")
      (node (ref "ESP1") (pin "34") (pinfunction "IO38_34") (pintype "unspecified"))
    )
    (net (code "119") (name "unconnected-(ESP1-IO39-Pad35)") (class "Default")
      (node (ref "ESP1") (pin "35") (pinfunction "IO39_35") (pintype "unspecified"))
    )
    (net (code "120") (name "unconnected-(ESP1-IO40-Pad36)") (class "Default")
      (node (ref "ESP1") (pin "36") (pinfunction "IO40_36") (pintype "unspecified"))
    )
    (net (code "121") (name "unconnected-(ESP1-IO41-Pad37)") (class "Default")
      (node (ref "ESP1") (pin "37") (pinfunction "IO41_37") (pintype "unspecified"))
    )
    (net (code "122") (name "unconnected-(ESP1-IO42-Pad38)") (class "Default")
      (node (ref "ESP1") (pin "38") (pinfunction "IO42_38") (pintype "unspecified"))
    )
    (net (code "123") (name "unconnected-(ESP1-IO45-Pad41)") (class "Default")
      (node (ref "ESP1") (pin "41") (pinfunction "IO45_41") (pintype "unspecified"))
    )
    (net (code "124") (name "unconnected-(ESP1-IO46-Pad44)") (class "Default")
      (node (ref "ESP1") (pin "44") (pinfunction "IO46_44") (pintype "unspecified"))
    )
    (net (code "125") (name "unconnected-(ESP1-IO47-Pad27)") (class "Default")
      (node (ref "ESP1") (pin "27") (pinfunction "IO47_27") (pintype "unspecified"))
    )
    (net (code "126") (name "unconnected-(ESP1-IO48-Pad30)") (class "Default")
      (node (ref "ESP1") (pin "30") (pinfunction "IO48_30") (pintype "unspecified"))
    )
    (net (code "127") (name "unconnected-(ESP1-RXD0-Pad40)") (class "Default")
      (node (ref "ESP1") (pin "40") (pinfunction "RXD0_40") (pintype "unspecified"))
    )
    (net (code "128") (name "unconnected-(ESP1-TXD0-Pad39)") (class "Default")
      (node (ref "ESP1") (pin "39") (pinfunction "TXD0_39") (pintype "unspecified"))
    )
    (net (code "129") (name "unconnected-(RF4-GND-Pad3)") (class "Default")
      (node (ref "RF4") (pin "3") (pinfunction "GND_3") (pintype "unspecified"))
    )
    (net (code "130") (name "unconnected-(U2-ADC-Pad25)") (class "Default")
      (node (ref "U2") (pin "25") (pinfunction "ADC_25") (pintype "unspecified+no_connect"))
    )
    (net (code "131") (name "unconnected-(U2-CAM_I2C_SCL-Pad118)") (class "Default")
      (node (ref "U2") (pin "118") (pinfunction "CAM_I2C_SCL_118") (pintype "unspecified+no_connect"))
    )
    (net (code "132") (name "unconnected-(U2-CAM_I2C_SDA-Pad117)") (class "Default")
      (node (ref "U2") (pin "117") (pinfunction "CAM_I2C_SDA_117") (pintype "unspecified+no_connect"))
    )
    (net (code "133") (name "unconnected-(U2-CAM_MCLK-Pad121)") (class "Default")
      (node (ref "U2") (pin "121") (pinfunction "CAM_MCLK_121") (pintype "unspecified+no_connect"))
    )
    (net (code "134") (name "unconnected-(U2-CAM_PWDN-Pad119)") (class "Default")
      (node (ref "U2") (pin "119") (pinfunction "CAM_PWDN_119") (pintype "unspecified+no_connect"))
    )
    (net (code "135") (name "unconnected-(U2-CAM_RST-Pad120)") (class "Default")
      (node (ref "U2") (pin "120") (pinfunction "CAM_RST_120") (pintype "unspecified+no_connect"))
    )
    (net (code "136") (name "unconnected-(U2-CAM_SPI_CLK-Pad124)") (class "Default")
      (node (ref "U2") (pin "124") (pinfunction "CAM_SPI_CLK_124") (pintype "unspecified+no_connect"))
    )
    (net (code "137") (name "unconnected-(U2-CAM_SPI_D0-Pad122)") (class "Default")
      (node (ref "U2") (pin "122") (pinfunction "CAM_SPI_D0_122") (pintype "unspecified+no_connect"))
    )
    (net (code "138") (name "unconnected-(U2-CAM_SPI_D1-Pad123)") (class "Default")
      (node (ref "U2") (pin "123") (pinfunction "CAM_SPI_D1_123") (pintype "unspecified+no_connect"))
    )
    (net (code "139") (name "unconnected-(U2-DCD-Pad5)") (class "Default")
      (node (ref "U2") (pin "5") (pinfunction "DCD_5") (pintype "unspecified+no_connect"))
    )
    (net (code "140") (name "unconnected-(U2-GPIO2-Pad26)") (class "Default")
      (node (ref "U2") (pin "26") (pinfunction "GPIO2_26") (pintype "unspecified"))
    )
    (net (code "141") (name "unconnected-(U2-I2C_SCL-Pad38)") (class "Default")
      (node (ref "U2") (pin "38") (pinfunction "I2C_SCL_38") (pintype "unspecified+no_connect"))
    )
    (net (code "142") (name "unconnected-(U2-I2C_SDA-Pad37)") (class "Default")
      (node (ref "U2") (pin "37") (pinfunction "I2C_SDA_37") (pintype "unspecified+no_connect"))
    )
    (net (code "143") (name "unconnected-(U2-LCD_BL_PWM-Pad101)") (class "Default")
      (node (ref "U2") (pin "101") (pinfunction "LCD_BL_PWM_101") (pintype "unspecified+no_connect"))
    )
    (net (code "144") (name "unconnected-(U2-LCD_DCX-Pad107)") (class "Default")
      (node (ref "U2") (pin "107") (pinfunction "LCD_DCX_107") (pintype "unspecified+no_connect"))
    )
    (net (code "145") (name "unconnected-(U2-LCD_RST-Pad106)") (class "Default")
      (node (ref "U2") (pin "106") (pinfunction "LCD_RST_106") (pintype "unspecified+no_connect"))
    )
    (net (code "146") (name "unconnected-(U2-LCD_SPI_CLK-Pad102)") (class "Default")
      (node (ref "U2") (pin "102") (pinfunction "LCD_SPI_CLK_102") (pintype "unspecified+no_connect"))
    )
    (net (code "147") (name "unconnected-(U2-LCD_SPI_CS-Pad105)") (class "Default")
      (node (ref "U2") (pin "105") (pinfunction "LCD_SPI_CS_105") (pintype "unspecified+no_connect"))
    )
    (net (code "148") (name "unconnected-(U2-LCD_SPI_RXD-Pad104)") (class "Default")
      (node (ref "U2") (pin "104") (pinfunction "LCD_SPI_RXD_104") (pintype "unspecified+no_connect"))
    )
    (net (code "149") (name "unconnected-(U2-LCD_SPI_TXD-Pad103)") (class "Default")
      (node (ref "U2") (pin "103") (pinfunction "LCD_SPI_TXD_103") (pintype "unspecified+no_connect"))
    )
    (net (code "150") (name "unconnected-(U2-MK_IN_2-Pad47)") (class "Default")
      (node (ref "U2") (pin "47") (pinfunction "MK_IN_2_47") (pintype "unspecified+no_connect"))
    )
    (net (code "151") (name "unconnected-(U2-MK_IN_5-Pad68)") (class "Default")
      (node (ref "U2") (pin "68") (pinfunction "MK_IN_5_68") (pintype "unspecified"))
    )
    (net (code "152") (name "unconnected-(U2-MK_IN_6{slash}I2C3_SCL-Pad36)") (class "Default")
      (node (ref "U2") (pin "36") (pinfunction "MK_IN_6/I2C3_SCL_36") (pintype "unspecified"))
    )
    (net (code "153") (name "unconnected-(U2-MK_OUT_2-Pad44)") (class "Default")
      (node (ref "U2") (pin "44") (pinfunction "MK_OUT_2_44") (pintype "unspecified+no_connect"))
    )
    (net (code "154") (name "unconnected-(U2-MK_OUT_3-Pad21)") (class "Default")
      (node (ref "U2") (pin "21") (pinfunction "MK_OUT_3_21") (pintype "unspecified"))
    )
    (net (code "155") (name "unconnected-(U2-MK_OUT_5-Pad67)") (class "Default")
      (node (ref "U2") (pin "67") (pinfunction "MK_OUT_5_67") (pintype "unspecified"))
    )
    (net (code "156") (name "unconnected-(U2-MK_OUT_6{slash}I2C3_SDA-Pad35)") (class "Default")
      (node (ref "U2") (pin "35") (pinfunction "MK_OUT_6/I2C3_SDA_35") (pintype "unspecified"))
    )
    (net (code "157") (name "unconnected-(U2-NC-Pad113)") (class "Default")
      (node (ref "U2") (pin "113") (pinfunction "NC_113") (pintype "unspecified+no_connect"))
    )
    (net (code "158") (name "unconnected-(U2-NC-Pad114)") (class "Default")
      (node (ref "U2") (pin "114") (pinfunction "NC_114") (pintype "unspecified+no_connect"))
    )
    (net (code "159") (name "unconnected-(U2-NC-Pad115)") (class "Default")
      (node (ref "U2") (pin "115") (pinfunction "NC_115") (pintype "unspecified+no_connect"))
    )
    (net (code "160") (name "unconnected-(U2-RESET-Pad16)") (class "Default")
      (node (ref "U2") (pin "16") (pinfunction "RESET_16") (pintype "unspecified+no_connect"))
    )
    (net (code "161") (name "unconnected-(U2-SPI_CLK-Pad11)") (class "Default")
      (node (ref "U2") (pin "11") (pinfunction "SPI_CLK_11") (pintype "unspecified"))
    )
    (net (code "162") (name "unconnected-(U2-SPI_CS-Pad12)") (class "Default")
      (node (ref "U2") (pin "12") (pinfunction "SPI_CS_12") (pintype "unspecified"))
    )
    (net (code "163") (name "unconnected-(U2-SPI_MISO-Pad14)") (class "Default")
      (node (ref "U2") (pin "14") (pinfunction "SPI_MISO_14") (pintype "unspecified"))
    )
    (net (code "164") (name "unconnected-(U2-SPI_MOSI-Pad13)") (class "Default")
      (node (ref "U2") (pin "13") (pinfunction "SPI_MOSI_13") (pintype "unspecified"))
    )
    (net (code "165") (name "unconnected-(U2-UART_LOG_RX-Pad22)") (class "Default")
      (node (ref "U2") (pin "22") (pinfunction "UART_LOG_RX_22") (pintype "unspecified+no_connect"))
    )
    (net (code "166") (name "unconnected-(U2-UART_LOG_TX-Pad23)") (class "Default")
      (node (ref "U2") (pin "23") (pinfunction "UART_LOG_TX_23") (pintype "unspecified+no_connect"))
    )
    (net (code "167") (name "unconnected-(U2-USIM1_DET-Pad34)") (class "Default")
      (node (ref "U2") (pin "34") (pinfunction "USIM1_DET_34") (pintype "unspecified+no_connect"))
    )
    (net (code "168") (name "unconnected-(U2-USIM2_CLK-Pad109)") (class "Default")
      (node (ref "U2") (pin "109") (pinfunction "USIM2_CLK_109") (pintype "unspecified+no_connect"))
    )
    (net (code "169") (name "unconnected-(U2-USIM2_DATA-Pad108)") (class "Default")
      (node (ref "U2") (pin "108") (pinfunction "USIM2_DATA_108") (pintype "unspecified+no_connect"))
    )
    (net (code "170") (name "unconnected-(U2-USIM2_DET-Pad112)") (class "Default")
      (node (ref "U2") (pin "112") (pinfunction "USIM2_DET_112") (pintype "unspecified+no_connect"))
    )
    (net (code "171") (name "unconnected-(U2-USIM2_RST-Pad111)") (class "Default")
      (node (ref "U2") (pin "111") (pinfunction "USIM2_RST_111") (pintype "unspecified+no_connect"))
    )
    (net (code "172") (name "unconnected-(U2-USIM2_VDD-Pad110)") (class "Default")
      (node (ref "U2") (pin "110") (pinfunction "USIM2_VDD_110") (pintype "unspecified+no_connect"))
    )
    (net (code "173") (name "unconnected-(USB2-SBU1-PadA8)") (class "Default")
      (node (ref "USB2") (pin "A8") (pinfunction "SBU1_A8") (pintype "unspecified+no_connect"))
    )
    (net (code "174") (name "unconnected-(USB2-SBU2-PadB8)") (class "Default")
      (node (ref "USB2") (pin "B8") (pinfunction "SBU2_B8") (pintype "unspecified+no_connect"))
    )
  )
)
